# CLOCK.net
KiCad netlist of a schematic drawn in Altium Designer
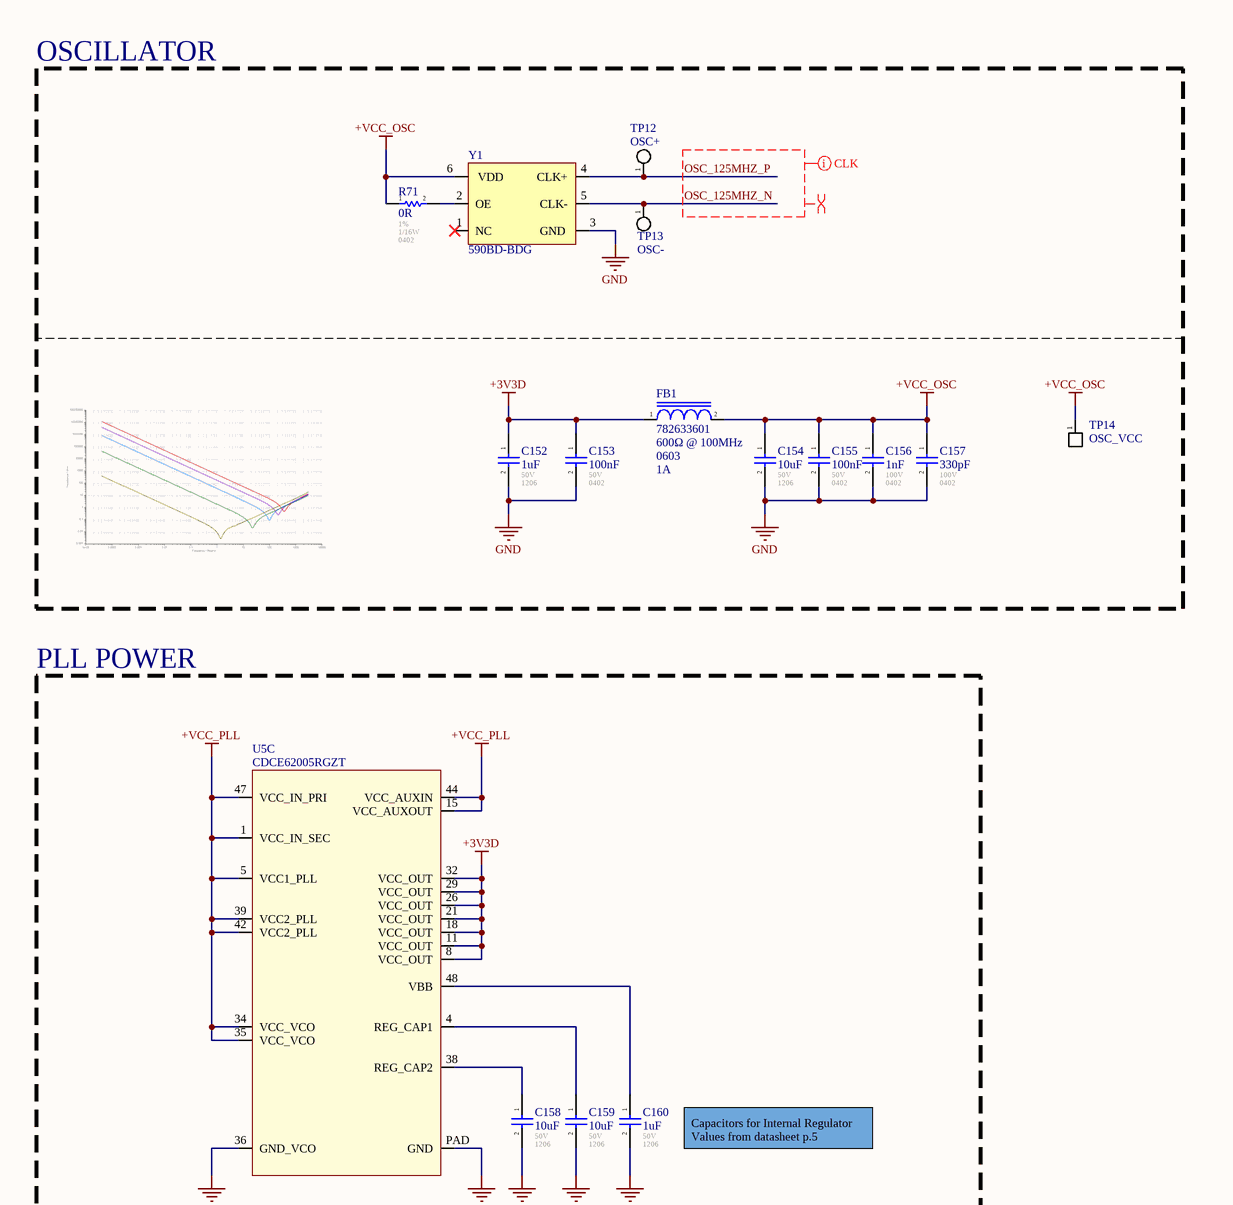
[diagram p0: CLOCK.SchDoc, top left]
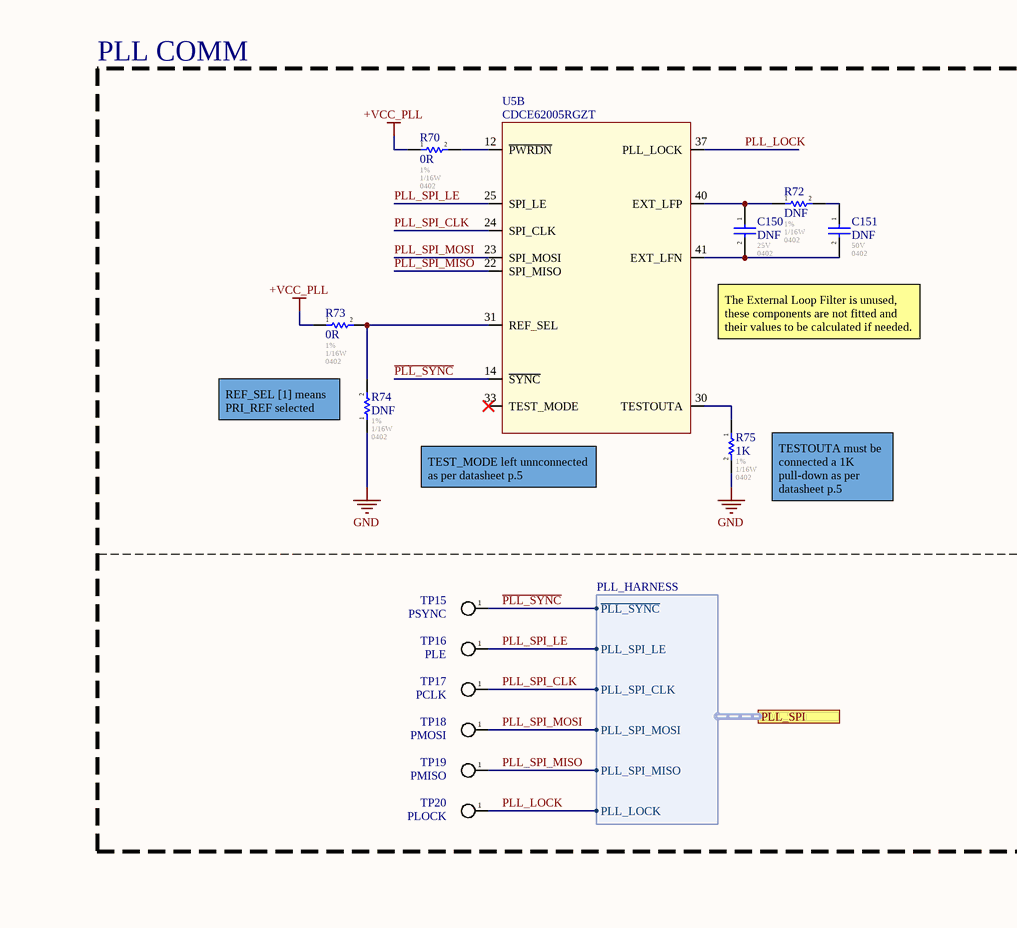
[diagram p1: CLOCK.SchDoc, top right]
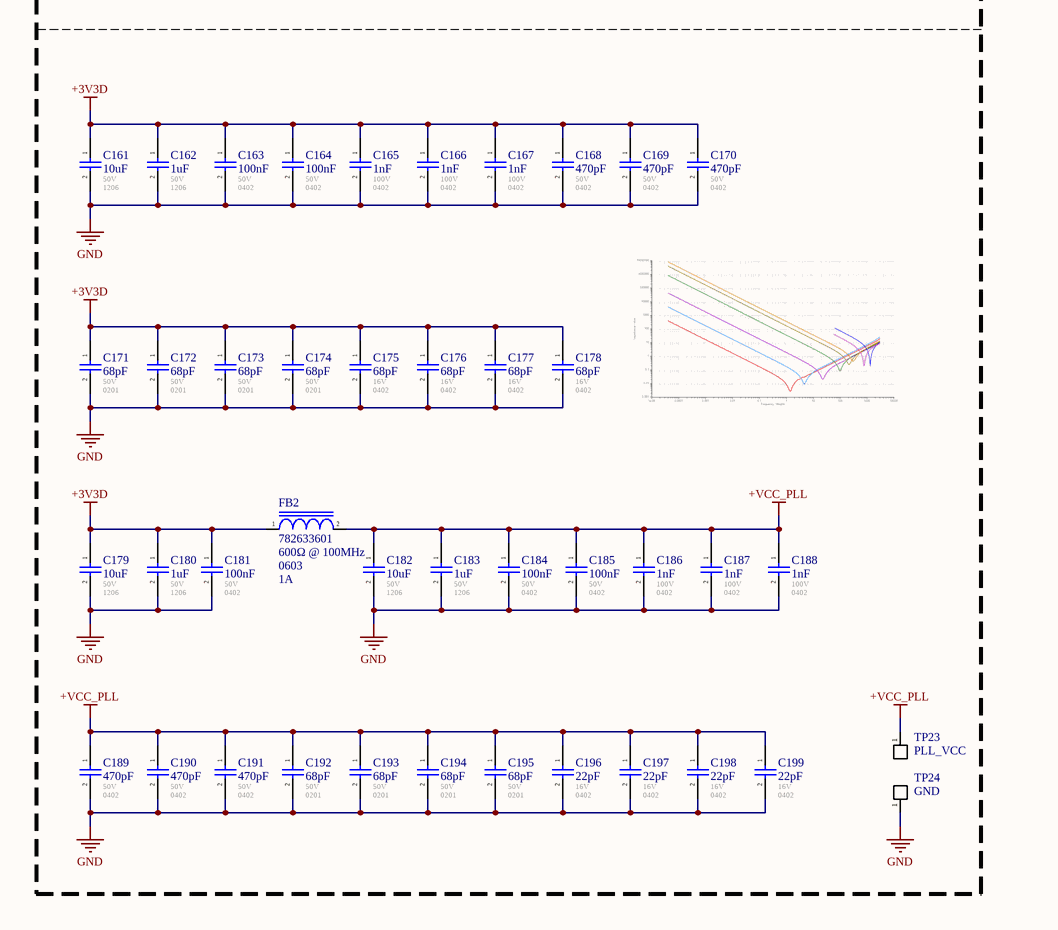
[diagram p2: CLOCK.SchDoc, bottom left]
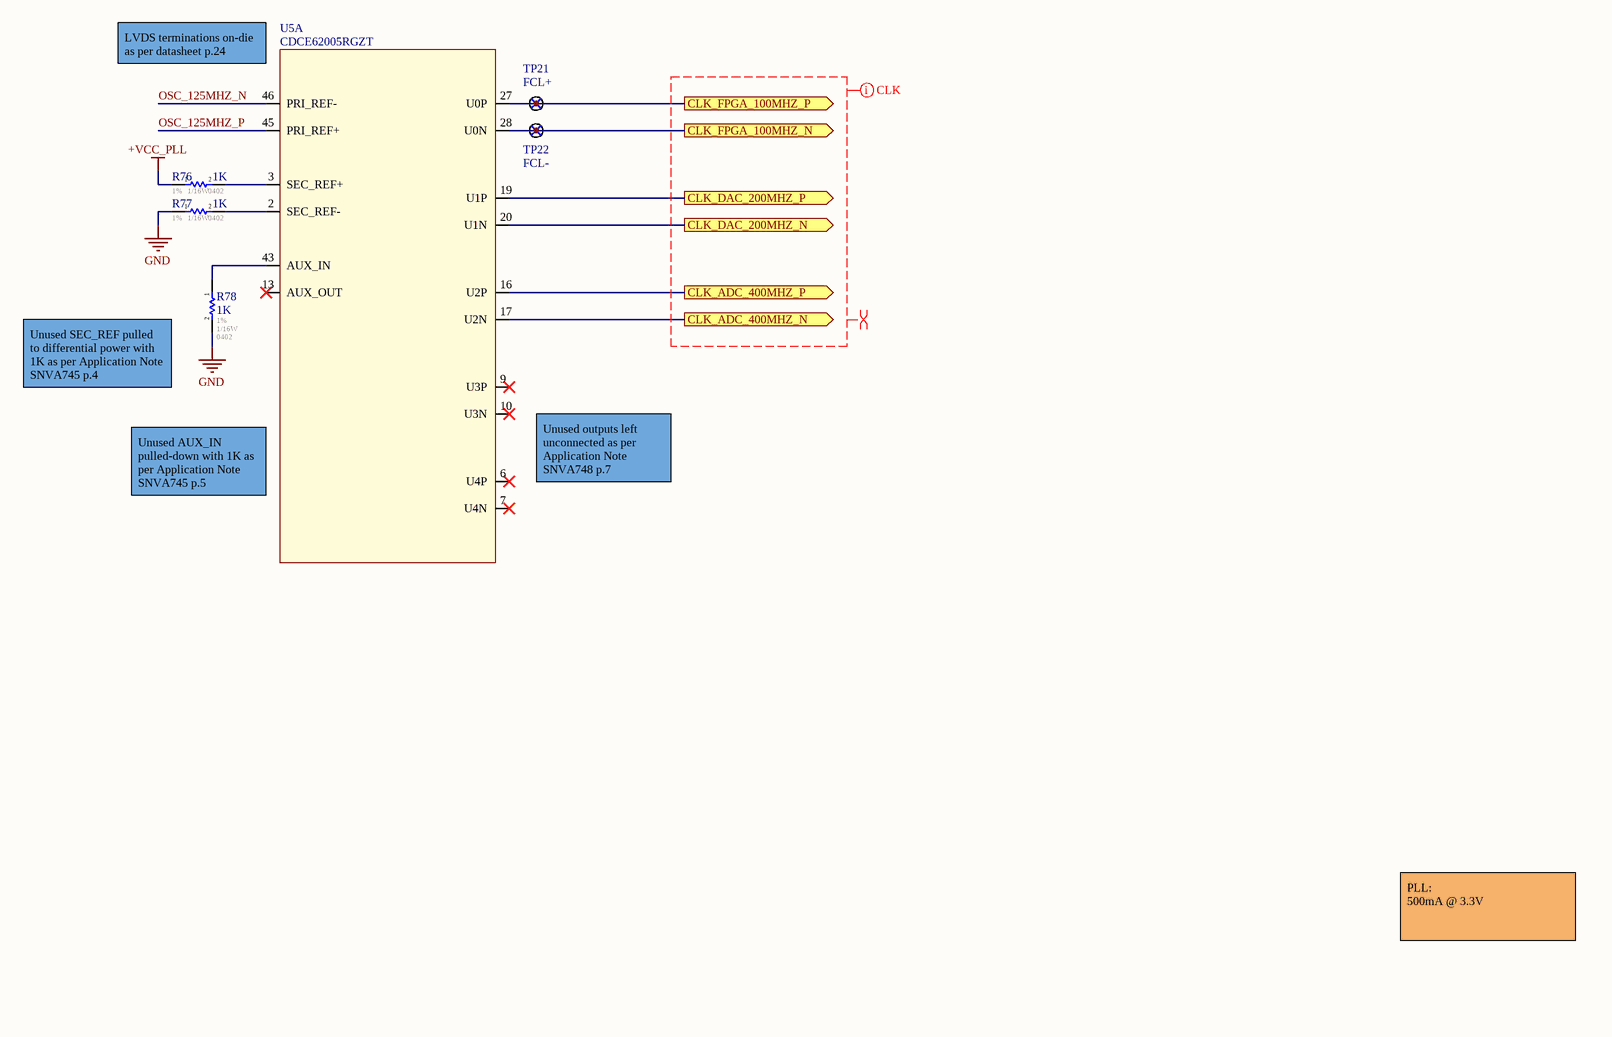
[diagram p3: CLOCK.SchDoc, bottom right]

(export (version "E")
  (design (tool "Eeschema 10.0.6"))
  (components
    (comp (ref "C150")
      (value "DNF")
      (footprint "0402")
      (fields (field (name "VOLTAGE - RATED") "25V"))
      (libsource (lib "Symbols") (part "CAP_CER"))
    )
    (comp (ref "C151")
      (value "DNF")
      (footprint "0402")
      (description "0402 100nF X7R Ceramic Capacitor")
      (fields (field (name "VOLTAGE - RATED") "50V"))
      (libsource (lib "Symbols") (part "CAP_CER"))
    )
    (comp (ref "C152")
      (value "1uF")
      (footprint "1206")
      (description "GCJ31CR71H105KA12L\r\n1206 1uF 10% X7R Ceramic Capacitor")
      (fields
        (field (name "MFR") "Murata")
        (field (name "PART#") "GCJ31CR71H105KA12L")
        (field (name "VOLTAGE - RATED") "50V")
      )
      (libsource (lib "Symbols") (part "CAP_CER"))
    )
    (comp (ref "C153")
      (value "100nF")
      (footprint "0402")
      (description "GCM155R71H104KE02J\r\n0402 100nF 10% X7R Ceramic Capacitor")
      (fields
        (field (name "MFR") "Murata")
        (field (name "PART#") "GCM155R71H104KE02J")
        (field (name "VOLTAGE - RATED") "50V")
      )
      (libsource (lib "Symbols") (part "CAP_CER"))
    )
    (comp (ref "C154")
      (value "10uF")
      (footprint "1206")
      (description "GRT31CR61H106KE01L\r\n1206 10uF 10% X5R Ceramic Capacitor")
      (fields
        (field (name "MFR") "Murata")
        (field (name "VOLTAGE - RATED") "50V")
        (field (name "TOLERANCE") "10%")
      )
      (libsource (lib "Symbols") (part "CAP_CER"))
    )
    (comp (ref "C155")
      (value "100nF")
      (footprint "0402")
      (description "GCM155R71H104KE02J\r\n0402 100nF 10% X7R Ceramic Capacitor")
      (fields
        (field (name "MFR") "Murata")
        (field (name "PART#") "GCM155R71H104KE02J")
        (field (name "VOLTAGE - RATED") "50V")
      )
      (libsource (lib "Symbols") (part "CAP_CER"))
    )
    (comp (ref "C156")
      (value "1nF")
      (footprint "0402")
      (description "GCM155R72A102KA37D\r\n0402 1nF 10% X7R Ceramic Capacitor")
      (fields
        (field (name "MFR") "Murata")
        (field (name "PART#") "GCM155R72A102KA37D")
        (field (name "VOLTAGE - RATED") "100V")
      )
      (libsource (lib "Symbols") (part "CAP_CER"))
    )
    (comp (ref "C157")
      (value "330pF")
      (footprint "0402")
      (description "GCM155R72A331KA37D\r\n0402 330pF 10% X7R Ceramic Capacitor")
      (fields
        (field (name "MFR") "Murata")
        (field (name "PART#") "GCM155R72A331KA37D")
        (field (name "VOLTAGE - RATED") "100V")
      )
      (libsource (lib "Symbols") (part "CAP_CER"))
    )
    (comp (ref "C158")
      (value "10uF")
      (footprint "1206")
      (description "GRT31CR61H106KE01L\r\n1206 10uF 10% X5R Ceramic Capacitor")
      (fields
        (field (name "MFR") "Murata")
        (field (name "VOLTAGE - RATED") "50V")
        (field (name "TOLERANCE") "10%")
      )
      (libsource (lib "Symbols") (part "CAP_CER"))
    )
    (comp (ref "C159")
      (value "10uF")
      (footprint "1206")
      (description "GRT31CR61H106KE01L\r\n1206 10uF 10% X5R Ceramic Capacitor")
      (fields
        (field (name "MFR") "Murata")
        (field (name "VOLTAGE - RATED") "50V")
        (field (name "TOLERANCE") "10%")
      )
      (libsource (lib "Symbols") (part "CAP_CER"))
    )
    (comp (ref "C160")
      (value "1uF")
      (footprint "1206")
      (description "GCJ31CR71H105KA12L\r\n1206 1uF 10% X7R Ceramic Capacitor")
      (fields
        (field (name "MFR") "Murata")
        (field (name "PART#") "GCJ31CR71H105KA12L")
        (field (name "VOLTAGE - RATED") "50V")
      )
      (libsource (lib "Symbols") (part "CAP_CER"))
    )
    (comp (ref "C161")
      (value "10uF")
      (footprint "1206")
      (description "GRT31CR61H106KE01L\r\n1206 10uF 10% X5R Ceramic Capacitor")
      (fields
        (field (name "MFR") "Murata")
        (field (name "VOLTAGE - RATED") "50V")
        (field (name "TOLERANCE") "10%")
      )
      (libsource (lib "Symbols") (part "CAP_CER"))
    )
    (comp (ref "C162")
      (value "1uF")
      (footprint "1206")
      (description "GCJ31CR71H105KA12L\r\n1206 1uF 10% X7R Ceramic Capacitor")
      (fields
        (field (name "MFR") "Murata")
        (field (name "PART#") "GCJ31CR71H105KA12L")
        (field (name "VOLTAGE - RATED") "50V")
      )
      (libsource (lib "Symbols") (part "CAP_CER"))
    )
    (comp (ref "C163")
      (value "100nF")
      (footprint "0402")
      (description "GCM155R71H104KE02J\r\n0402 100nF 10% X7R Ceramic Capacitor")
      (fields
        (field (name "MFR") "Murata")
        (field (name "PART#") "GCM155R71H104KE02J")
        (field (name "VOLTAGE - RATED") "50V")
      )
      (libsource (lib "Symbols") (part "CAP_CER"))
    )
    (comp (ref "C164")
      (value "100nF")
      (footprint "0402")
      (description "GCM155R71H104KE02J\r\n0402 100nF 10% X7R Ceramic Capacitor")
      (fields
        (field (name "MFR") "Murata")
        (field (name "PART#") "GCM155R71H104KE02J")
        (field (name "VOLTAGE - RATED") "50V")
      )
      (libsource (lib "Symbols") (part "CAP_CER"))
    )
    (comp (ref "C165")
      (value "1nF")
      (footprint "0402")
      (description "GCM155R72A102KA37D\r\n0402 1nF 10% X7R Ceramic Capacitor")
      (fields
        (field (name "MFR") "Murata")
        (field (name "PART#") "GCM155R72A102KA37D")
        (field (name "VOLTAGE - RATED") "100V")
      )
      (libsource (lib "Symbols") (part "CAP_CER"))
    )
    (comp (ref "C166")
      (value "1nF")
      (footprint "0402")
      (description "GCM155R72A102KA37D\r\n0402 1nF 10% X7R Ceramic Capacitor")
      (fields
        (field (name "MFR") "Murata")
        (field (name "PART#") "GCM155R72A102KA37D")
        (field (name "VOLTAGE - RATED") "100V")
      )
      (libsource (lib "Symbols") (part "CAP_CER"))
    )
    (comp (ref "C167")
      (value "1nF")
      (footprint "0402")
      (description "GCM155R72A102KA37D\r\n0402 1nF 10% X7R Ceramic Capacitor")
      (fields
        (field (name "MFR") "Murata")
        (field (name "PART#") "GCM155R72A102KA37D")
        (field (name "VOLTAGE - RATED") "100V")
      )
      (libsource (lib "Symbols") (part "CAP_CER"))
    )
    (comp (ref "C168")
      (value "470pF")
      (footprint "0402")
      (description "GCM155R71H471KA37J\r\n0402 470pF 10% X7R Ceramic Capacitor")
      (fields
        (field (name "MFR") "Murata")
        (field (name "PART#") "GCM155R71H471KA37J")
        (field (name "VOLTAGE - RATED") "50V")
      )
      (libsource (lib "Symbols") (part "CAP_CER"))
    )
    (comp (ref "C169")
      (value "470pF")
      (footprint "0402")
      (description "GCM155R71H471KA37J\r\n0402 470pF 10% X7R Ceramic Capacitor")
      (fields
        (field (name "MFR") "Murata")
        (field (name "PART#") "GCM155R71H471KA37J")
        (field (name "VOLTAGE - RATED") "50V")
      )
      (libsource (lib "Symbols") (part "CAP_CER"))
    )
    (comp (ref "C170")
      (value "470pF")
      (footprint "0402")
      (description "GCM155R71H471KA37J\r\n0402 470pF 10% X7R Ceramic Capacitor")
      (fields
        (field (name "MFR") "Murata")
        (field (name "PART#") "GCM155R71H471KA37J")
        (field (name "VOLTAGE - RATED") "50V")
      )
      (libsource (lib "Symbols") (part "CAP_CER"))
    )
    (comp (ref "C171")
      (value "68pF")
      (footprint "0201")
      (description "0201 68pF 5% C0G 50V Ceramic Capacitor\r\nCGA1A2C0G1H680J030BA")
      (fields
        (field (name "MFR") "TDK")
        (field (name "PART#") "CGA1A2C0G1H680J030BA")
        (field (name "VOLTAGE - RATED") "50V")
      )
      (libsource (lib "Symbols") (part "CAP_CER"))
    )
    (comp (ref "C172")
      (value "68pF")
      (footprint "0201")
      (description "0201 68pF 5% C0G 50V Ceramic Capacitor\r\nCGA1A2C0G1H680J030BA")
      (fields
        (field (name "MFR") "TDK")
        (field (name "PART#") "CGA1A2C0G1H680J030BA")
        (field (name "VOLTAGE - RATED") "50V")
      )
      (libsource (lib "Symbols") (part "CAP_CER"))
    )
    (comp (ref "C173")
      (value "68pF")
      (footprint "0201")
      (description "0201 68pF 5% C0G 50V Ceramic Capacitor\r\nCGA1A2C0G1H680J030BA")
      (fields
        (field (name "MFR") "TDK")
        (field (name "PART#") "CGA1A2C0G1H680J030BA")
        (field (name "VOLTAGE - RATED") "50V")
      )
      (libsource (lib "Symbols") (part "CAP_CER"))
    )
    (comp (ref "C174")
      (value "68pF")
      (footprint "0201")
      (description "0201 68pF 5% C0G 50V Ceramic Capacitor\r\nCGA1A2C0G1H680J030BA")
      (fields
        (field (name "MFR") "TDK")
        (field (name "PART#") "CGA1A2C0G1H680J030BA")
        (field (name "VOLTAGE - RATED") "50V")
      )
      (libsource (lib "Symbols") (part "CAP_CER"))
    )
    (comp (ref "C175")
      (value "68pF")
      (footprint "0402")
      (description "0402 22pF 10% X7R 16V Ceramic Capacitor\r\nC0402C220K4RACAUTO")
      (fields
        (field (name "MFR") "KEMET")
        (field (name "PART#") "C0402C220K4RACAUTO")
        (field (name "VOLTAGE - RATED") "16V")
      )
      (libsource (lib "Symbols") (part "CAP_CER"))
    )
    (comp (ref "C176")
      (value "68pF")
      (footprint "0402")
      (description "0402 22pF 10% X7R 16V Ceramic Capacitor\r\nC0402C220K4RACAUTO")
      (fields
        (field (name "MFR") "KEMET")
        (field (name "PART#") "C0402C220K4RACAUTO")
        (field (name "VOLTAGE - RATED") "16V")
      )
      (libsource (lib "Symbols") (part "CAP_CER"))
    )
    (comp (ref "C177")
      (value "68pF")
      (footprint "0402")
      (description "0402 22pF 10% X7R 16V Ceramic Capacitor\r\nC0402C220K4RACAUTO")
      (fields
        (field (name "MFR") "KEMET")
        (field (name "PART#") "C0402C220K4RACAUTO")
        (field (name "VOLTAGE - RATED") "16V")
      )
      (libsource (lib "Symbols") (part "CAP_CER"))
    )
    (comp (ref "C178")
      (value "68pF")
      (footprint "0402")
      (description "0402 22pF 10% X7R 16V Ceramic Capacitor\r\nC0402C220K4RACAUTO")
      (fields
        (field (name "MFR") "KEMET")
        (field (name "PART#") "C0402C220K4RACAUTO")
        (field (name "VOLTAGE - RATED") "16V")
      )
      (libsource (lib "Symbols") (part "CAP_CER"))
    )
    (comp (ref "C179")
      (value "10uF")
      (footprint "1206")
      (description "GRT31CR61H106KE01L\r\n1206 10uF 10% X5R Ceramic Capacitor")
      (fields
        (field (name "MFR") "Murata")
        (field (name "VOLTAGE - RATED") "50V")
        (field (name "TOLERANCE") "10%")
      )
      (libsource (lib "Symbols") (part "CAP_CER"))
    )
    (comp (ref "C180")
      (value "1uF")
      (footprint "1206")
      (description "GCJ31CR71H105KA12L\r\n1206 1uF 10% X7R Ceramic Capacitor")
      (fields
        (field (name "MFR") "Murata")
        (field (name "PART#") "GCJ31CR71H105KA12L")
        (field (name "VOLTAGE - RATED") "50V")
      )
      (libsource (lib "Symbols") (part "CAP_CER"))
    )
    (comp (ref "C181")
      (value "100nF")
      (footprint "0402")
      (description "GCM155R71H104KE02J\r\n0402 100nF 10% X7R Ceramic Capacitor")
      (fields
        (field (name "MFR") "Murata")
        (field (name "PART#") "GCM155R71H104KE02J")
        (field (name "VOLTAGE - RATED") "50V")
      )
      (libsource (lib "Symbols") (part "CAP_CER"))
    )
    (comp (ref "C182")
      (value "10uF")
      (footprint "1206")
      (description "GRT31CR61H106KE01L\r\n1206 10uF 10% X5R Ceramic Capacitor")
      (fields
        (field (name "MFR") "Murata")
        (field (name "VOLTAGE - RATED") "50V")
        (field (name "TOLERANCE") "10%")
      )
      (libsource (lib "Symbols") (part "CAP_CER"))
    )
    (comp (ref "C183")
      (value "1uF")
      (footprint "1206")
      (description "GCJ31CR71H105KA12L\r\n1206 1uF 10% X7R Ceramic Capacitor")
      (fields
        (field (name "MFR") "Murata")
        (field (name "PART#") "GCJ31CR71H105KA12L")
        (field (name "VOLTAGE - RATED") "50V")
      )
      (libsource (lib "Symbols") (part "CAP_CER"))
    )
    (comp (ref "C184")
      (value "100nF")
      (footprint "0402")
      (description "GCM155R71H104KE02J\r\n0402 100nF 10% X7R Ceramic Capacitor")
      (fields
        (field (name "MFR") "Murata")
        (field (name "PART#") "GCM155R71H104KE02J")
        (field (name "VOLTAGE - RATED") "50V")
      )
      (libsource (lib "Symbols") (part "CAP_CER"))
    )
    (comp (ref "C185")
      (value "100nF")
      (footprint "0402")
      (description "GCM155R71H104KE02J\r\n0402 100nF 10% X7R Ceramic Capacitor")
      (fields
        (field (name "MFR") "Murata")
        (field (name "PART#") "GCM155R71H104KE02J")
        (field (name "VOLTAGE - RATED") "50V")
      )
      (libsource (lib "Symbols") (part "CAP_CER"))
    )
    (comp (ref "C186")
      (value "1nF")
      (footprint "0402")
      (description "GCM155R72A102KA37D\r\n0402 1nF 10% X7R Ceramic Capacitor")
      (fields
        (field (name "MFR") "Murata")
        (field (name "PART#") "GCM155R72A102KA37D")
        (field (name "VOLTAGE - RATED") "100V")
      )
      (libsource (lib "Symbols") (part "CAP_CER"))
    )
    (comp (ref "C187")
      (value "1nF")
      (footprint "0402")
      (description "GCM155R72A102KA37D\r\n0402 1nF 10% X7R Ceramic Capacitor")
      (fields
        (field (name "MFR") "Murata")
        (field (name "PART#") "GCM155R72A102KA37D")
        (field (name "VOLTAGE - RATED") "100V")
      )
      (libsource (lib "Symbols") (part "CAP_CER"))
    )
    (comp (ref "C188")
      (value "1nF")
      (footprint "0402")
      (description "GCM155R72A102KA37D\r\n0402 1nF 10% X7R Ceramic Capacitor")
      (fields
        (field (name "MFR") "Murata")
        (field (name "PART#") "GCM155R72A102KA37D")
        (field (name "VOLTAGE - RATED") "100V")
      )
      (libsource (lib "Symbols") (part "CAP_CER"))
    )
    (comp (ref "C189")
      (value "470pF")
      (footprint "0402")
      (description "GCM155R71H471KA37J\r\n0402 470pF 10% X7R Ceramic Capacitor")
      (fields
        (field (name "MFR") "Murata")
        (field (name "PART#") "GCM155R71H471KA37J")
        (field (name "VOLTAGE - RATED") "50V")
      )
      (libsource (lib "Symbols") (part "CAP_CER"))
    )
    (comp (ref "C190")
      (value "470pF")
      (footprint "0402")
      (description "GCM155R71H471KA37J\r\n0402 470pF 10% X7R Ceramic Capacitor")
      (fields
        (field (name "MFR") "Murata")
        (field (name "PART#") "GCM155R71H471KA37J")
        (field (name "VOLTAGE - RATED") "50V")
      )
      (libsource (lib "Symbols") (part "CAP_CER"))
    )
    (comp (ref "C191")
      (value "470pF")
      (footprint "0402")
      (description "GCM155R71H471KA37J\r\n0402 470pF 10% X7R Ceramic Capacitor")
      (fields
        (field (name "MFR") "Murata")
        (field (name "PART#") "GCM155R71H471KA37J")
        (field (name "VOLTAGE - RATED") "50V")
      )
      (libsource (lib "Symbols") (part "CAP_CER"))
    )
    (comp (ref "C192")
      (value "68pF")
      (footprint "0201")
      (description "0201 68pF 5% C0G 50V Ceramic Capacitor\r\nCGA1A2C0G1H680J030BA")
      (fields
        (field (name "MFR") "TDK")
        (field (name "PART#") "CGA1A2C0G1H680J030BA")
        (field (name "VOLTAGE - RATED") "50V")
      )
      (libsource (lib "Symbols") (part "CAP_CER"))
    )
    (comp (ref "C193")
      (value "68pF")
      (footprint "0201")
      (description "0201 68pF 5% C0G 50V Ceramic Capacitor\r\nCGA1A2C0G1H680J030BA")
      (fields
        (field (name "MFR") "TDK")
        (field (name "PART#") "CGA1A2C0G1H680J030BA")
        (field (name "VOLTAGE - RATED") "50V")
      )
      (libsource (lib "Symbols") (part "CAP_CER"))
    )
    (comp (ref "C194")
      (value "68pF")
      (footprint "0201")
      (description "0201 68pF 5% C0G 50V Ceramic Capacitor\r\nCGA1A2C0G1H680J030BA")
      (fields
        (field (name "MFR") "TDK")
        (field (name "PART#") "CGA1A2C0G1H680J030BA")
        (field (name "VOLTAGE - RATED") "50V")
      )
      (libsource (lib "Symbols") (part "CAP_CER"))
    )
    (comp (ref "C195")
      (value "68pF")
      (footprint "0201")
      (description "0201 68pF 5% C0G 50V Ceramic Capacitor\r\nCGA1A2C0G1H680J030BA")
      (fields
        (field (name "MFR") "TDK")
        (field (name "PART#") "CGA1A2C0G1H680J030BA")
        (field (name "VOLTAGE - RATED") "50V")
      )
      (libsource (lib "Symbols") (part "CAP_CER"))
    )
    (comp (ref "C196")
      (value "22pF")
      (footprint "0402")
      (description "0402 22pF 10% X7R 16V Ceramic Capacitor\r\nC0402C220K4RACAUTO")
      (fields
        (field (name "MFR") "KEMET")
        (field (name "PART#") "C0402C220K4RACAUTO")
        (field (name "VOLTAGE - RATED") "16V")
      )
      (libsource (lib "Symbols") (part "CAP_CER"))
    )
    (comp (ref "C197")
      (value "22pF")
      (footprint "0402")
      (description "0402 22pF 10% X7R 16V Ceramic Capacitor\r\nC0402C220K4RACAUTO")
      (fields
        (field (name "MFR") "KEMET")
        (field (name "PART#") "C0402C220K4RACAUTO")
        (field (name "VOLTAGE - RATED") "16V")
      )
      (libsource (lib "Symbols") (part "CAP_CER"))
    )
    (comp (ref "C198")
      (value "22pF")
      (footprint "0402")
      (description "0402 22pF 10% X7R 16V Ceramic Capacitor\r\nC0402C220K4RACAUTO")
      (fields
        (field (name "MFR") "KEMET")
        (field (name "PART#") "C0402C220K4RACAUTO")
        (field (name "VOLTAGE - RATED") "16V")
      )
      (libsource (lib "Symbols") (part "CAP_CER"))
    )
    (comp (ref "C199")
      (value "22pF")
      (footprint "0402")
      (description "0402 22pF 10% X7R 16V Ceramic Capacitor\r\nC0402C220K4RACAUTO")
      (fields
        (field (name "MFR") "KEMET")
        (field (name "PART#") "C0402C220K4RACAUTO")
        (field (name "VOLTAGE - RATED") "16V")
      )
      (libsource (lib "Symbols") (part "CAP_CER"))
    )
    (comp (ref "FB1")
      (value "782633601")
      (footprint "IND_0603")
      (description "600 Ohms @ 100 MHz 1 Signal Line Ferrite Bead 0603 (1608 Metric) 1A 200mOhm")
      (fields
        (field (name "IMPEDANCE @ FREQ") "600Ω @ 100MHz")
        (field (name "PACKAGE / CASE") "0603")
        (field (name "CURRENT RATING") "1A")
        (field (name "MANUFACTURER") "Wurth Elektronik")
      )
      (libsource (lib "Symbols") (part "FERRITE_BEAD"))
    )
    (comp (ref "FB2")
      (value "782633601")
      (footprint "IND_0603")
      (description "600 Ohms @ 100 MHz 1 Signal Line Ferrite Bead 0603 (1608 Metric) 1A 200mOhm")
      (fields
        (field (name "IMPEDANCE @ FREQ") "600Ω @ 100MHz")
        (field (name "PACKAGE / CASE") "0603")
        (field (name "CURRENT RATING") "1A")
        (field (name "MANUFACTURER") "Wurth Elektronik")
      )
      (libsource (lib "Symbols") (part "FERRITE_BEAD"))
    )
    (comp (ref "R70")
      (value "0R")
      (footprint "RES_0402")
      (fields
        (field (name "TOLERANCE") "1%")
        (field (name "POWER") "1/16W")
        (field (name "PACKAGE / CASE") "0402")
      )
      (libsource (lib "Symbols") (part "RESISTOR"))
    )
    (comp (ref "R71")
      (value "0R")
      (footprint "RES_0402")
      (fields
        (field (name "TOLERANCE") "1%")
        (field (name "POWER") "1/16W")
        (field (name "PACKAGE / CASE") "0402")
      )
      (libsource (lib "Symbols") (part "RESISTOR"))
    )
    (comp (ref "R72")
      (value "DNF")
      (footprint "RES_0402")
      (fields
        (field (name "TOLERANCE") "1%")
        (field (name "POWER") "1/16W")
        (field (name "PACKAGE / CASE") "0402")
      )
      (libsource (lib "Symbols") (part "RESISTOR"))
    )
    (comp (ref "R73")
      (value "0R")
      (footprint "RES_0402")
      (fields
        (field (name "TOLERANCE") "1%")
        (field (name "POWER") "1/16W")
        (field (name "PACKAGE / CASE") "0402")
      )
      (libsource (lib "Symbols") (part "RESISTOR"))
    )
    (comp (ref "R74")
      (value "DNF")
      (footprint "RES_0402")
      (fields
        (field (name "TOLERANCE") "1%")
        (field (name "POWER") "1/16W")
        (field (name "PACKAGE / CASE") "0402")
      )
      (libsource (lib "Symbols") (part "RESISTOR"))
    )
    (comp (ref "R75")
      (value "1K")
      (footprint "RES_0402")
      (fields
        (field (name "TOLERANCE") "1%")
        (field (name "POWER") "1/16W")
        (field (name "PACKAGE / CASE") "0402")
      )
      (libsource (lib "Symbols") (part "RESISTOR"))
    )
    (comp (ref "R76")
      (value "1K")
      (footprint "RES_0402")
      (fields
        (field (name "TOLERANCE") "1%")
        (field (name "POWER") "1/16W")
        (field (name "PACKAGE / CASE") "0402")
      )
      (libsource (lib "Symbols") (part "RESISTOR"))
    )
    (comp (ref "R77")
      (value "1K")
      (footprint "RES_0402")
      (fields
        (field (name "TOLERANCE") "1%")
        (field (name "POWER") "1/16W")
        (field (name "PACKAGE / CASE") "0402")
      )
      (libsource (lib "Symbols") (part "RESISTOR"))
    )
    (comp (ref "R78")
      (value "1K")
      (footprint "RES_0402")
      (fields
        (field (name "TOLERANCE") "1%")
        (field (name "POWER") "1/16W")
        (field (name "PACKAGE / CASE") "0402")
      )
      (libsource (lib "Symbols") (part "RESISTOR"))
    )
    (comp (ref "TP12")
      (value "OSC+")
      (footprint "TP_PAD_SMALL")
      (description "Test Point")
      (libsource (lib "Symbols") (part "TESTPOINT_PAD_SMALL"))
    )
    (comp (ref "TP13")
      (value "OSC-")
      (footprint "TP_PAD_SMALL")
      (description "Test Point")
      (libsource (lib "Symbols") (part "TESTPOINT_PAD_SMALL"))
    )
    (comp (ref "TP14")
      (value "OSC_VCC")
      (footprint "TP_PAD")
      (description "Test Point")
      (libsource (lib "Symbols") (part "TESTPOINT_PAD"))
    )
    (comp (ref "TP15")
      (value "PSYNC")
      (footprint "TP_PAD_SMALL")
      (description "Test Point")
      (libsource (lib "Symbols") (part "TESTPOINT_PAD_SMALL"))
    )
    (comp (ref "TP16")
      (value "PLE")
      (footprint "TP_PAD_SMALL")
      (description "Test Point")
      (libsource (lib "Symbols") (part "TESTPOINT_PAD_SMALL"))
    )
    (comp (ref "TP17")
      (value "PCLK")
      (footprint "TP_PAD_SMALL")
      (description "Test Point")
      (libsource (lib "Symbols") (part "TESTPOINT_PAD_SMALL"))
    )
    (comp (ref "TP18")
      (value "PMOSI")
      (footprint "TP_PAD_SMALL")
      (description "Test Point")
      (libsource (lib "Symbols") (part "TESTPOINT_PAD_SMALL"))
    )
    (comp (ref "TP19")
      (value "PMISO")
      (footprint "TP_PAD_SMALL")
      (description "Test Point")
      (libsource (lib "Symbols") (part "TESTPOINT_PAD_SMALL"))
    )
    (comp (ref "TP20")
      (value "PLOCK")
      (footprint "TP_PAD_SMALL")
      (description "Test Point")
      (libsource (lib "Symbols") (part "TESTPOINT_PAD_SMALL"))
    )
    (comp (ref "TP21")
      (value "FCL+")
      (footprint "TP_PAD_TINY")
      (description "Test Point")
      (libsource (lib "Symbols") (part "TESTPOINT_PAD_TINY"))
    )
    (comp (ref "TP22")
      (value "FCL-")
      (footprint "TP_PAD_TINY")
      (description "Test Point")
      (libsource (lib "Symbols") (part "TESTPOINT_PAD_TINY"))
    )
    (comp (ref "TP23")
      (value "PLL_VCC")
      (footprint "TP_PAD")
      (description "Test Point")
      (libsource (lib "Symbols") (part "TESTPOINT_PAD"))
    )
    (comp (ref "TP24")
      (value "GND")
      (footprint "TP_PAD")
      (description "Test Point")
      (libsource (lib "Symbols") (part "TESTPOINT_PAD"))
    )
    (comp (ref "U5")
      (value "CDCE62005RGZT")
      (footprint "TIM_CDCE62005RGZT")
      (description "TIM - CLK SYNTH JITTER CLEANER 3:5 - QFN-48")
      (fields
        (field (name "VOLTAGE") "3 V ~ 3.6 V")
        (field (name "MFG") "Texas Instruments")
        (field (name "CREATEDBY") "Jonathan Bouchard")
      )
      (libsource (lib "S7CAS_LIB2023") (part "TIM_CDCE62005RGZT"))
    )
    (comp (ref "Y1")
      (value "590BD-BDG")
      (footprint "OSC_590BD-BDG")
      (description "TIM - OSC PROG 125MHz ~ 214.999MHz LVDS 3.3V 7PPM EN/DS - 6-SMD")
      (fields
        (field (name "CREATEDBY/DATE") "from 590BD-CDG")
        (field (name "VERIFIEDBY") "Caroline Paulin / 3/10/2019")
      )
      (libsource (lib "S7CAS_LIB2023") (part "OSC_590BD-BDG"))
    )
  )
  (nets
    (net (code "2") (name "+3V3D") (class "Default")
      (node (ref "C152") (pin "1") (pinfunction "1_1") (pintype "passive"))
      (node (ref "C153") (pin "1") (pinfunction "1_1") (pintype "passive"))
      (node (ref "C161") (pin "1") (pinfunction "1_1") (pintype "passive"))
      (node (ref "C162") (pin "1") (pinfunction "1_1") (pintype "passive"))
      (node (ref "C163") (pin "1") (pinfunction "1_1") (pintype "passive"))
      (node (ref "C164") (pin "1") (pinfunction "1_1") (pintype "passive"))
      (node (ref "C165") (pin "1") (pinfunction "1_1") (pintype "passive"))
      (node (ref "C166") (pin "1") (pinfunction "1_1") (pintype "passive"))
      (node (ref "C167") (pin "1") (pinfunction "1_1") (pintype "passive"))
      (node (ref "C168") (pin "1") (pinfunction "1_1") (pintype "passive"))
      (node (ref "C169") (pin "1") (pinfunction "1_1") (pintype "passive"))
      (node (ref "C170") (pin "1") (pinfunction "1_1") (pintype "passive"))
      (node (ref "C171") (pin "1") (pinfunction "1_1") (pintype "passive"))
      (node (ref "C172") (pin "1") (pinfunction "1_1") (pintype "passive"))
      (node (ref "C173") (pin "1") (pinfunction "1_1") (pintype "passive"))
      (node (ref "C174") (pin "1") (pinfunction "1_1") (pintype "passive"))
      (node (ref "C175") (pin "1") (pinfunction "1_1") (pintype "passive"))
      (node (ref "C176") (pin "1") (pinfunction "1_1") (pintype "passive"))
      (node (ref "C177") (pin "1") (pinfunction "1_1") (pintype "passive"))
      (node (ref "C178") (pin "1") (pinfunction "1_1") (pintype "passive"))
      (node (ref "C179") (pin "1") (pinfunction "1_1") (pintype "passive"))
      (node (ref "C180") (pin "1") (pinfunction "1_1") (pintype "passive"))
      (node (ref "C181") (pin "1") (pinfunction "1_1") (pintype "passive"))
      (node (ref "FB1") (pin "1") (pinfunction "1_1") (pintype "passive"))
      (node (ref "FB2") (pin "1") (pinfunction "1_1") (pintype "passive"))
      (node (ref "U5") (pin "11") (pinfunction "VCC_OUT_11") (pintype "passive"))
      (node (ref "U5") (pin "18") (pinfunction "VCC_OUT_18") (pintype "passive"))
      (node (ref "U5") (pin "21") (pinfunction "VCC_OUT_21") (pintype "passive"))
      (node (ref "U5") (pin "26") (pinfunction "VCC_OUT_26") (pintype "passive"))
      (node (ref "U5") (pin "29") (pinfunction "VCC_OUT_29") (pintype "passive"))
      (node (ref "U5") (pin "32") (pinfunction "VCC_OUT_32") (pintype "passive"))
      (node (ref "U5") (pin "8") (pinfunction "VCC_OUT_8") (pintype "passive"))
    )
    (net (code "3") (name "+VCC_OSC") (class "Default")
      (node (ref "C154") (pin "1") (pinfunction "1_1") (pintype "passive"))
      (node (ref "C155") (pin "1") (pinfunction "1_1") (pintype "passive"))
      (node (ref "C156") (pin "1") (pinfunction "1_1") (pintype "passive"))
      (node (ref "C157") (pin "1") (pinfunction "1_1") (pintype "passive"))
      (node (ref "FB1") (pin "2") (pinfunction "2_2") (pintype "passive"))
      (node (ref "R71") (pin "1") (pinfunction "1_1") (pintype "passive"))
      (node (ref "TP14") (pin "1") (pinfunction "A_1") (pintype "passive"))
      (node (ref "Y1") (pin "6") (pinfunction "VDD_6") (pintype "passive"))
    )
    (net (code "4") (name "+VCC_PLL") (class "Default")
      (node (ref "C182") (pin "1") (pinfunction "1_1") (pintype "passive"))
      (node (ref "C183") (pin "1") (pinfunction "1_1") (pintype "passive"))
      (node (ref "C184") (pin "1") (pinfunction "1_1") (pintype "passive"))
      (node (ref "C185") (pin "1") (pinfunction "1_1") (pintype "passive"))
      (node (ref "C186") (pin "1") (pinfunction "1_1") (pintype "passive"))
      (node (ref "C187") (pin "1") (pinfunction "1_1") (pintype "passive"))
      (node (ref "C188") (pin "1") (pinfunction "1_1") (pintype "passive"))
      (node (ref "C189") (pin "1") (pinfunction "1_1") (pintype "passive"))
      (node (ref "C190") (pin "1") (pinfunction "1_1") (pintype "passive"))
      (node (ref "C191") (pin "1") (pinfunction "1_1") (pintype "passive"))
      (node (ref "C192") (pin "1") (pinfunction "1_1") (pintype "passive"))
      (node (ref "C193") (pin "1") (pinfunction "1_1") (pintype "passive"))
      (node (ref "C194") (pin "1") (pinfunction "1_1") (pintype "passive"))
      (node (ref "C195") (pin "1") (pinfunction "1_1") (pintype "passive"))
      (node (ref "C196") (pin "1") (pinfunction "1_1") (pintype "passive"))
      (node (ref "C197") (pin "1") (pinfunction "1_1") (pintype "passive"))
      (node (ref "C198") (pin "1") (pinfunction "1_1") (pintype "passive"))
      (node (ref "C199") (pin "1") (pinfunction "1_1") (pintype "passive"))
      (node (ref "FB2") (pin "2") (pinfunction "2_2") (pintype "passive"))
      (node (ref "R70") (pin "1") (pinfunction "1_1") (pintype "passive"))
      (node (ref "R73") (pin "1") (pinfunction "1_1") (pintype "passive"))
      (node (ref "R76") (pin "1") (pinfunction "1_1") (pintype "passive"))
      (node (ref "TP23") (pin "1") (pinfunction "A_1") (pintype "passive"))
      (node (ref "U5") (pin "1") (pinfunction "VCC_IN_SEC_1") (pintype "passive"))
      (node (ref "U5") (pin "15") (pinfunction "VCC_AUXOUT_15") (pintype "passive"))
      (node (ref "U5") (pin "34") (pinfunction "VCC_VCO_34") (pintype "passive"))
      (node (ref "U5") (pin "35") (pinfunction "VCC_VCO_35") (pintype "passive"))
      (node (ref "U5") (pin "39") (pinfunction "VCC2_PLL_39") (pintype "passive"))
      (node (ref "U5") (pin "42") (pinfunction "VCC2_PLL_42") (pintype "passive"))
      (node (ref "U5") (pin "44") (pinfunction "VCC_AUXIN_44") (pintype "passive"))
      (node (ref "U5") (pin "47") (pinfunction "VCC_IN_PRI_47") (pintype "passive"))
      (node (ref "U5") (pin "5") (pinfunction "VCC1_PLL_5") (pintype "passive"))
    )
    (net (code "5") (name "/CLK_ADC_400MHZ_N") (class "Default")
      (node (ref "U5") (pin "17") (pinfunction "U2N_17") (pintype "passive"))
    )
    (net (code "6") (name "/CLK_ADC_400MHZ_P") (class "Default")
      (node (ref "U5") (pin "16") (pinfunction "U2P_16") (pintype "passive"))
    )
    (net (code "7") (name "/CLK_DAC_200MHZ_N") (class "Default")
      (node (ref "U5") (pin "20") (pinfunction "U1N_20") (pintype "passive"))
    )
    (net (code "8") (name "/CLK_DAC_200MHZ_P") (class "Default")
      (node (ref "U5") (pin "19") (pinfunction "U1P_19") (pintype "passive"))
    )
    (net (code "9") (name "/CLK_FPGA_100MHZ_N") (class "Default")
      (node (ref "TP22") (pin "1") (pinfunction "A_1") (pintype "passive"))
      (node (ref "U5") (pin "28") (pinfunction "U0N_28") (pintype "passive"))
    )
    (net (code "10") (name "/CLK_FPGA_100MHZ_P") (class "Default")
      (node (ref "TP21") (pin "1") (pinfunction "A_1") (pintype "passive"))
      (node (ref "U5") (pin "27") (pinfunction "U0P_27") (pintype "passive"))
    )
    (net (code "11") (name "/OSC_125MHZ_N") (class "Default")
      (node (ref "TP13") (pin "1") (pinfunction "A_1") (pintype "passive"))
      (node (ref "U5") (pin "46") (pinfunction "PRI_REF-_46") (pintype "passive"))
      (node (ref "Y1") (pin "5") (pinfunction "CLK-_5") (pintype "passive"))
    )
    (net (code "12") (name "/OSC_125MHZ_P") (class "Default")
      (node (ref "TP12") (pin "1") (pinfunction "A_1") (pintype "passive"))
      (node (ref "U5") (pin "45") (pinfunction "PRI_REF+_45") (pintype "passive"))
      (node (ref "Y1") (pin "4") (pinfunction "CLK+_4") (pintype "passive"))
    )
    (net (code "13") (name "/PLL_LOCK") (class "Default")
      (node (ref "TP20") (pin "1") (pinfunction "A_1") (pintype "passive"))
      (node (ref "U5") (pin "37") (pinfunction "PLL_LOCK_37") (pintype "passive"))
    )
    (net (code "14") (name "/PLL_SPI_CLK") (class "Default")
      (node (ref "TP17") (pin "1") (pinfunction "A_1") (pintype "passive"))
      (node (ref "U5") (pin "24") (pinfunction "SPI_CLK_24") (pintype "passive"))
    )
    (net (code "15") (name "/PLL_SPI_LE") (class "Default")
      (node (ref "TP16") (pin "1") (pinfunction "A_1") (pintype "passive"))
      (node (ref "U5") (pin "25") (pinfunction "SPI_LE_25") (pintype "passive"))
    )
    (net (code "16") (name "/PLL_SPI_MISO") (class "Default")
      (node (ref "TP19") (pin "1") (pinfunction "A_1") (pintype "passive"))
      (node (ref "U5") (pin "22") (pinfunction "SPI_MISO_22") (pintype "passive"))
    )
    (net (code "17") (name "/PLL_SPI_MOSI") (class "Default")
      (node (ref "TP18") (pin "1") (pinfunction "A_1") (pintype "passive"))
      (node (ref "U5") (pin "23") (pinfunction "SPI_MOSI_23") (pintype "passive"))
    )
    (net (code "18") (name "/PLL_SYNC") (class "Default")
      (node (ref "TP15") (pin "1") (pinfunction "A_1") (pintype "passive"))
      (node (ref "U5") (pin "14") (pinfunction "~{SYNC}_14") (pintype "passive"))
    )
    (net (code "20") (name "GND") (class "Default")
      (node (ref "C152") (pin "2") (pinfunction "2_2") (pintype "passive"))
      (node (ref "C153") (pin "2") (pinfunction "2_2") (pintype "passive"))
      (node (ref "C154") (pin "2") (pinfunction "2_2") (pintype "passive"))
      (node (ref "C155") (pin "2") (pinfunction "2_2") (pintype "passive"))
      (node (ref "C156") (pin "2") (pinfunction "2_2") (pintype "passive"))
      (node (ref "C157") (pin "2") (pinfunction "2_2") (pintype "passive"))
      (node (ref "C158") (pin "2") (pinfunction "2_2") (pintype "passive"))
      (node (ref "C159") (pin "2") (pinfunction "2_2") (pintype "passive"))
      (node (ref "C160") (pin "2") (pinfunction "2_2") (pintype "passive"))
      (node (ref "C161") (pin "2") (pinfunction "2_2") (pintype "passive"))
      (node (ref "C162") (pin "2") (pinfunction "2_2") (pintype "passive"))
      (node (ref "C163") (pin "2") (pinfunction "2_2") (pintype "passive"))
      (node (ref "C164") (pin "2") (pinfunction "2_2") (pintype "passive"))
      (node (ref "C165") (pin "2") (pinfunction "2_2") (pintype "passive"))
      (node (ref "C166") (pin "2") (pinfunction "2_2") (pintype "passive"))
      (node (ref "C167") (pin "2") (pinfunction "2_2") (pintype "passive"))
      (node (ref "C168") (pin "2") (pinfunction "2_2") (pintype "passive"))
      (node (ref "C169") (pin "2") (pinfunction "2_2") (pintype "passive"))
      (node (ref "C170") (pin "2") (pinfunction "2_2") (pintype "passive"))
      (node (ref "C171") (pin "2") (pinfunction "2_2") (pintype "passive"))
      (node (ref "C172") (pin "2") (pinfunction "2_2") (pintype "passive"))
      (node (ref "C173") (pin "2") (pinfunction "2_2") (pintype "passive"))
      (node (ref "C174") (pin "2") (pinfunction "2_2") (pintype "passive"))
      (node (ref "C175") (pin "2") (pinfunction "2_2") (pintype "passive"))
      (node (ref "C176") (pin "2") (pinfunction "2_2") (pintype "passive"))
      (node (ref "C177") (pin "2") (pinfunction "2_2") (pintype "passive"))
      (node (ref "C178") (pin "2") (pinfunction "2_2") (pintype "passive"))
      (node (ref "C179") (pin "2") (pinfunction "2_2") (pintype "passive"))
      (node (ref "C180") (pin "2") (pinfunction "2_2") (pintype "passive"))
      (node (ref "C181") (pin "2") (pinfunction "2_2") (pintype "passive"))
      (node (ref "C182") (pin "2") (pinfunction "2_2") (pintype "passive"))
      (node (ref "C183") (pin "2") (pinfunction "2_2") (pintype "passive"))
      (node (ref "C184") (pin "2") (pinfunction "2_2") (pintype "passive"))
      (node (ref "C185") (pin "2") (pinfunction "2_2") (pintype "passive"))
      (node (ref "C186") (pin "2") (pinfunction "2_2") (pintype "passive"))
      (node (ref "C187") (pin "2") (pinfunction "2_2") (pintype "passive"))
      (node (ref "C188") (pin "2") (pinfunction "2_2") (pintype "passive"))
      (node (ref "C189") (pin "2") (pinfunction "2_2") (pintype "passive"))
      (node (ref "C190") (pin "2") (pinfunction "2_2") (pintype "passive"))
      (node (ref "C191") (pin "2") (pinfunction "2_2") (pintype "passive"))
      (node (ref "C192") (pin "2") (pinfunction "2_2") (pintype "passive"))
      (node (ref "C193") (pin "2") (pinfunction "2_2") (pintype "passive"))
      (node (ref "C194") (pin "2") (pinfunction "2_2") (pintype "passive"))
      (node (ref "C195") (pin "2") (pinfunction "2_2") (pintype "passive"))
      (node (ref "C196") (pin "2") (pinfunction "2_2") (pintype "passive"))
      (node (ref "C197") (pin "2") (pinfunction "2_2") (pintype "passive"))
      (node (ref "C198") (pin "2") (pinfunction "2_2") (pintype "passive"))
      (node (ref "C199") (pin "2") (pinfunction "2_2") (pintype "passive"))
      (node (ref "R74") (pin "1") (pinfunction "1_1") (pintype "passive"))
      (node (ref "R75") (pin "2") (pinfunction "2_2") (pintype "passive"))
      (node (ref "R77") (pin "1") (pinfunction "1_1") (pintype "passive"))
      (node (ref "R78") (pin "2") (pinfunction "2_2") (pintype "passive"))
      (node (ref "TP24") (pin "1") (pinfunction "A_1") (pintype "passive"))
      (node (ref "U5") (pin "36") (pinfunction "GND_VCO_36") (pintype "passive"))
      (node (ref "U5") (pin "PAD") (pinfunction "GND_PAD") (pintype "passive"))
      (node (ref "Y1") (pin "3") (pinfunction "GND_3") (pintype "passive"))
    )
    (net (code "21") (name "Net-(C151-Pad1)") (class "Default")
      (node (ref "C151") (pin "1") (pinfunction "1_1") (pintype "passive"))
      (node (ref "R72") (pin "2") (pinfunction "2_2") (pintype "passive"))
    )
    (net (code "22") (name "Net-(U5A-AUX_IN)") (class "Default")
      (node (ref "R78") (pin "1") (pinfunction "1_1") (pintype "passive"))
      (node (ref "U5") (pin "43") (pinfunction "AUX_IN_43") (pintype "passive"))
    )
    (net (code "23") (name "Net-(U5A-SEC_REF+)") (class "Default")
      (node (ref "R76") (pin "2") (pinfunction "2_2") (pintype "passive"))
      (node (ref "U5") (pin "3") (pinfunction "SEC_REF+_3") (pintype "passive"))
    )
    (net (code "24") (name "Net-(U5A-SEC_REF-)") (class "Default")
      (node (ref "R77") (pin "2") (pinfunction "2_2") (pintype "passive"))
      (node (ref "U5") (pin "2") (pinfunction "SEC_REF-_2") (pintype "passive"))
    )
    (net (code "25") (name "Net-(U5B-EXT_LFN)") (class "Default")
      (node (ref "C150") (pin "2") (pinfunction "2_2") (pintype "passive"))
      (node (ref "C151") (pin "2") (pinfunction "2_2") (pintype "passive"))
      (node (ref "U5") (pin "41") (pinfunction "EXT_LFN_41") (pintype "passive"))
    )
    (net (code "26") (name "Net-(U5B-EXT_LFP)") (class "Default")
      (node (ref "C150") (pin "1") (pinfunction "1_1") (pintype "passive"))
      (node (ref "R72") (pin "1") (pinfunction "1_1") (pintype "passive"))
      (node (ref "U5") (pin "40") (pinfunction "EXT_LFP_40") (pintype "passive"))
    )
    (net (code "27") (name "Net-(U5B-REF_SEL)") (class "Default")
      (node (ref "R73") (pin "2") (pinfunction "2_2") (pintype "passive"))
      (node (ref "R74") (pin "2") (pinfunction "2_2") (pintype "passive"))
      (node (ref "U5") (pin "31") (pinfunction "REF_SEL_31") (pintype "passive"))
    )
    (net (code "28") (name "Net-(U5B-TESTOUTA)") (class "Default")
      (node (ref "R75") (pin "1") (pinfunction "1_1") (pintype "passive"))
      (node (ref "U5") (pin "30") (pinfunction "TESTOUTA_30") (pintype "passive"))
    )
    (net (code "29") (name "Net-(U5B-~{PWRDN})") (class "Default")
      (node (ref "R70") (pin "2") (pinfunction "2_2") (pintype "passive"))
      (node (ref "U5") (pin "12") (pinfunction "~{PWRDN}_12") (pintype "passive"))
    )
    (net (code "30") (name "Net-(U5C-REG_CAP1)") (class "Default")
      (node (ref "C159") (pin "1") (pinfunction "1_1") (pintype "passive"))
      (node (ref "U5") (pin "4") (pinfunction "REG_CAP1_4") (pintype "passive"))
    )
    (net (code "31") (name "Net-(U5C-REG_CAP2)") (class "Default")
      (node (ref "C158") (pin "1") (pinfunction "1_1") (pintype "passive"))
      (node (ref "U5") (pin "38") (pinfunction "REG_CAP2_38") (pintype "passive"))
    )
    (net (code "32") (name "Net-(U5C-VBB)") (class "Default")
      (node (ref "C160") (pin "1") (pinfunction "1_1") (pintype "passive"))
      (node (ref "U5") (pin "48") (pinfunction "VBB_48") (pintype "passive"))
    )
    (net (code "33") (name "Net-(Y1-OE)") (class "Default")
      (node (ref "R71") (pin "2") (pinfunction "2_2") (pintype "passive"))
      (node (ref "Y1") (pin "2") (pinfunction "OE_2") (pintype "passive"))
    )
    (net (code "34") (name "unconnected-(U5A-AUX_OUT-Pad13)") (class "Default")
      (node (ref "U5") (pin "13") (pinfunction "AUX_OUT_13") (pintype "passive+no_connect"))
    )
    (net (code "35") (name "unconnected-(U5A-U3N-Pad10)") (class "Default")
      (node (ref "U5") (pin "10") (pinfunction "U3N_10") (pintype "passive+no_connect"))
    )
    (net (code "36") (name "unconnected-(U5A-U3P-Pad9)") (class "Default")
      (node (ref "U5") (pin "9") (pinfunction "U3P_9") (pintype "passive+no_connect"))
    )
    (net (code "37") (name "unconnected-(U5A-U4N-Pad7)") (class "Default")
      (node (ref "U5") (pin "7") (pinfunction "U4N_7") (pintype "passive+no_connect"))
    )
    (net (code "38") (name "unconnected-(U5A-U4P-Pad6)") (class "Default")
      (node (ref "U5") (pin "6") (pinfunction "U4P_6") (pintype "passive+no_connect"))
    )
    (net (code "39") (name "unconnected-(U5B-TEST_MODE-Pad33)") (class "Default")
      (node (ref "U5") (pin "33") (pinfunction "TEST_MODE_33") (pintype "passive+no_connect"))
    )
    (net (code "40") (name "unconnected-(Y1-NC-Pad1)") (class "Default")
      (node (ref "Y1") (pin "1") (pinfunction "NC_1") (pintype "passive+no_connect"))
    )
  )
)
